# V2-2layer.net
KiCad netlist of a schematic drawn in EAGLE
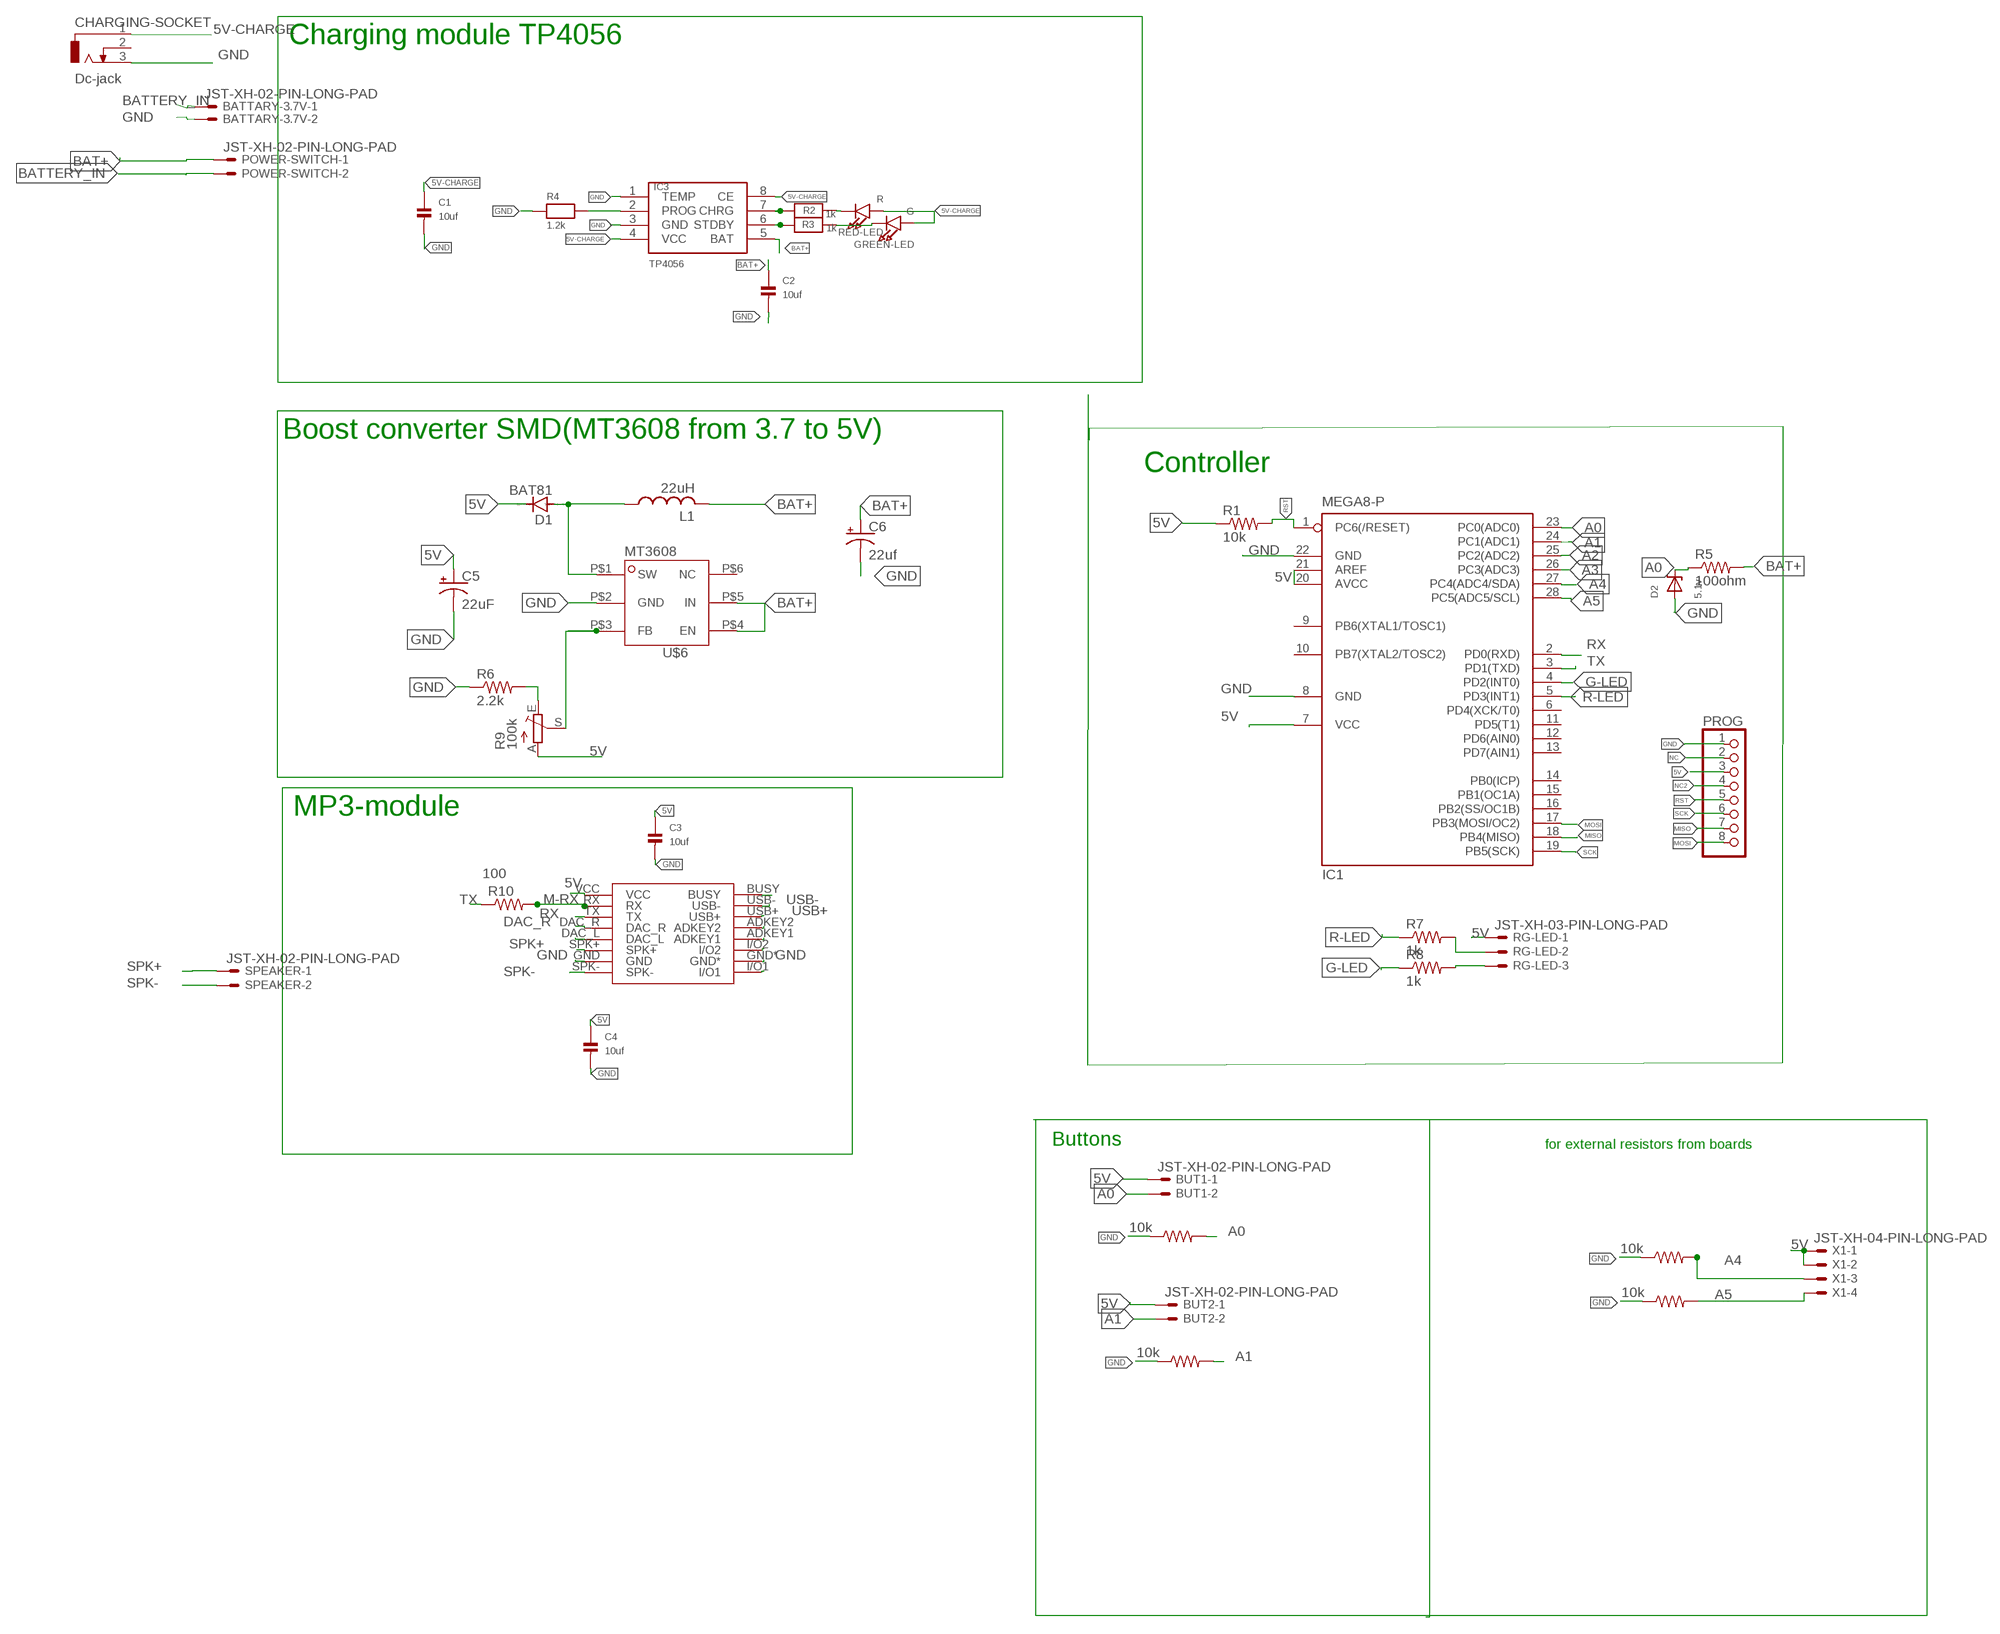
[diagram p0: schematic, sheet 1]

(export (version "E")
  (design (tool "Eeschema 10.0.6"))
  (components
    (comp (ref "BATTARY-3.7V")
      (value "JST-XH-02-PIN-LONG-PAD")
      (footprint "eagle-import:JST-XH-02-PACKAGE-LONG-PAD")
      (libsource (lib "eagle-import") (part "JST-XH-02-PIN-LONG-PAD"))
    )
    (comp (ref "BUT1")
      (value "JST-XH-02-PIN-LONG-PAD")
      (footprint "eagle-import:JST-XH-02-PACKAGE-LONG-PAD")
      (libsource (lib "eagle-import") (part "JST-XH-02-PIN-LONG-PAD"))
    )
    (comp (ref "BUT2")
      (value "JST-XH-02-PIN-LONG-PAD")
      (footprint "eagle-import:JST-XH-02-PACKAGE-LONG-PAD")
      (libsource (lib "eagle-import") (part "JST-XH-02-PIN-LONG-PAD"))
    )
    (comp (ref "C1")
      (value "10uf")
      (footprint "eagle-import:0805")
      (libsource (lib "eagle-import") (part "CAP_CERAMIC0805"))
    )
    (comp (ref "C2")
      (value "10uf")
      (footprint "eagle-import:0805")
      (libsource (lib "eagle-import") (part "CAP_CERAMIC0805"))
    )
    (comp (ref "C3")
      (value "10uf")
      (footprint "eagle-import:0805")
      (libsource (lib "eagle-import") (part "CAP_CERAMIC0805"))
    )
    (comp (ref "C4")
      (value "10uf")
      (footprint "eagle-import:0805")
      (libsource (lib "eagle-import") (part "CAP_CERAMIC0805"))
    )
    (comp (ref "C5")
      (value "22uF")
      (footprint "eagle-import:E2,5-6E")
      (libsource (lib "eagle-import") (part "CPOL-USE2,5-6E"))
    )
    (comp (ref "C6")
      (value "22uf")
      (footprint "eagle-import:E2,5-6E")
      (libsource (lib "eagle-import") (part "CPOL-USE2,5-6E"))
    )
    (comp (ref "CHARGING-SOCKET")
      (value "Dc-jack")
      (footprint "eagle-import:DCJ0303")
      (libsource (lib "eagle-import") (part "CON_JACK"))
    )
    (comp (ref "D1")
      (value "BAT81")
      (footprint "eagle-import:DO34-7")
      (libsource (lib "eagle-import") (part "BAT81"))
    )
    (comp (ref "D2")
      (value "5.1v")
      (footprint "eagle-import:SMADIODE")
      (libsource (lib "eagle-import") (part "DIODE-ZENER"))
    )
    (comp (ref "GREEN-LED")
      (value "G")
      (footprint "eagle-import:CHIPLED_0805")
      (libsource (lib "eagle-import") (part "LED0805"))
    )
    (comp (ref "IC1")
      (value "MEGA8-P")
      (footprint "eagle-import:DIL28-3")
      (libsource (lib "eagle-import") (part "MEGA8-P"))
    )
    (comp (ref "IC3")
      (value "TP4056")
      (footprint "eagle-import:SOP-8")
      (libsource (lib "eagle-import") (part "TP4056"))
    )
    (comp (ref "KEYPADS")
      (value "10k")
      (footprint "eagle-import:0204_7")
      (libsource (lib "eagle-import") (part "RES-7"))
    )
    (comp (ref "KEYPADS1")
      (value "10k")
      (footprint "eagle-import:0204_7")
      (libsource (lib "eagle-import") (part "RES-7"))
    )
    (comp (ref "KEYPADS2")
      (value "10k")
      (footprint "eagle-import:0204_7")
      (libsource (lib "eagle-import") (part "RES-7"))
    )
    (comp (ref "KEYPADS3")
      (value "10k")
      (footprint "eagle-import:0204_7")
      (libsource (lib "eagle-import") (part "RES-7"))
    )
    (comp (ref "L1")
      (value "22uH")
      (footprint "eagle-import:L1812")
      (libsource (lib "eagle-import") (part "L-USL1812"))
    )
    (comp (ref "POWER-SWITCH")
      (value "JST-XH-02-PIN-LONG-PAD")
      (footprint "eagle-import:JST-XH-02-PACKAGE-LONG-PAD")
      (libsource (lib "eagle-import") (part "JST-XH-02-PIN-LONG-PAD"))
    )
    (comp (ref "PROG")
      (value "PINHD-1X8")
      (footprint "eagle-import:1X08")
      (libsource (lib "eagle-import") (part "PINHD-1X8"))
    )
    (comp (ref "R1")
      (value "10k")
      (footprint "eagle-import:0204_7")
      (libsource (lib "eagle-import") (part "R-US_0204/7"))
    )
    (comp (ref "R2")
      (value "1k")
      (footprint "eagle-import:_0805")
      (libsource (lib "eagle-import") (part "RESISTOR_0805"))
    )
    (comp (ref "R3")
      (value "1k")
      (footprint "eagle-import:_0805")
      (libsource (lib "eagle-import") (part "RESISTOR_0805"))
    )
    (comp (ref "R4")
      (value "1.2k")
      (footprint "eagle-import:_0805")
      (libsource (lib "eagle-import") (part "RESISTOR_0805"))
    )
    (comp (ref "R5")
      (value "100ohm")
      (footprint "eagle-import:0204_7")
      (libsource (lib "eagle-import") (part "R-US_0204/7"))
    )
    (comp (ref "R6")
      (value "2.2k")
      (footprint "eagle-import:M0805")
      (libsource (lib "eagle-import") (part "R-US_M0805"))
    )
    (comp (ref "R7")
      (value "1k")
      (footprint "eagle-import:0204_7")
      (libsource (lib "eagle-import") (part "R-US_0204/7"))
    )
    (comp (ref "R8")
      (value "1k")
      (footprint "eagle-import:0204_7")
      (libsource (lib "eagle-import") (part "R-US_0204/7"))
    )
    (comp (ref "R9")
      (value "100k")
      (footprint "eagle-import:B25U")
      (libsource (lib "eagle-import") (part "TRIM_EU-B25U"))
    )
    (comp (ref "R10")
      (value "100")
      (footprint "eagle-import:0204_7")
      (libsource (lib "eagle-import") (part "RES-7"))
    )
    (comp (ref "RED-LED")
      (value "R")
      (footprint "eagle-import:CHIPLED_0805")
      (libsource (lib "eagle-import") (part "LED0805"))
    )
    (comp (ref "RG-LED")
      (value "JST-XH-03-PIN-LONG-PAD")
      (footprint "eagle-import:JST-XH-03-PACKAGE-LONG-PAD")
      (libsource (lib "eagle-import") (part "JST-XH-03-PIN-LONG-PAD"))
    )
    (comp (ref "SPEAKER")
      (value "JST-XH-02-PIN-LONG-PAD")
      (footprint "eagle-import:JST-XH-02-PACKAGE-LONG-PAD")
      (libsource (lib "eagle-import") (part "JST-XH-02-PIN-LONG-PAD"))
    )
    (comp (ref "U$2")
      (value "MP3_MODULE")
      (footprint "eagle-import:MP3_MODULE")
      (libsource (lib "eagle-import") (part "MP3_MODULE"))
    )
    (comp (ref "U$6")
      (value "MT3608SOT23-6")
      (footprint "eagle-import:SOT23-6")
      (libsource (lib "eagle-import") (part "MT3608SOT23-6"))
    )
    (comp (ref "X1")
      (value "JST-XH-04-PIN-LONG-PAD")
      (footprint "eagle-import:JST-XH-04-PACKAGE-LONG-PAD")
      (libsource (lib "eagle-import") (part "JST-XH-04-PIN-LONG-PAD"))
    )
  )
  (nets
    (net (code "1") (name "/DAC_R") (class "Default")
      (node (ref "U$2") (pin "DAC_R") (pinfunction "DAC_R_DAC_R") (pintype "bidirectional"))
    )
    (net (code "2") (name "/M-RX") (class "Default")
      (node (ref "R10") (pin "2") (pinfunction "2_2") (pintype "passive"))
      (node (ref "U$2") (pin "RX") (pinfunction "RX_RX") (pintype "bidirectional"))
    )
    (net (code "3") (name "/RX") (class "Default")
      (node (ref "IC1") (pin "2") (pinfunction "PD0(RXD)_2") (pintype "bidirectional"))
      (node (ref "U$2") (pin "TX") (pinfunction "TX_TX") (pintype "bidirectional"))
    )
    (net (code "4") (name "/SPK+") (class "Default")
      (node (ref "SPEAKER") (pin "1") (pinfunction "S_1") (pintype "passive"))
      (node (ref "U$2") (pin "SPK+") (pinfunction "SPK+_SPK+") (pintype "bidirectional"))
    )
    (net (code "5") (name "/SPK-") (class "Default")
      (node (ref "SPEAKER") (pin "2") (pinfunction "S_2") (pintype "passive"))
      (node (ref "U$2") (pin "SPK-") (pinfunction "SPK-_SPK-") (pintype "bidirectional"))
    )
    (net (code "6") (name "/TX") (class "Default")
      (node (ref "IC1") (pin "3") (pinfunction "PD1(TXD)_3") (pintype "bidirectional"))
      (node (ref "R10") (pin "1") (pinfunction "1_1") (pintype "passive"))
    )
    (net (code "7") (name "/USB+") (class "Default")
      (node (ref "U$2") (pin "USB+") (pinfunction "USB+_USB+") (pintype "bidirectional"))
    )
    (net (code "8") (name "/USB-") (class "Default")
      (node (ref "U$2") (pin "USB-") (pinfunction "USB-_USB-") (pintype "bidirectional"))
    )
    (net (code "9") (name "5V") (class "Default")
      (node (ref "BUT1") (pin "1") (pinfunction "S_1") (pintype "passive"))
      (node (ref "BUT2") (pin "1") (pinfunction "S_1") (pintype "passive"))
      (node (ref "C3") (pin "1") (pinfunction "P$1_1") (pintype "passive"))
      (node (ref "C4") (pin "1") (pinfunction "P$1_1") (pintype "passive"))
      (node (ref "C5") (pin "+") (pinfunction "+_+") (pintype "passive"))
      (node (ref "D1") (pin "C") (pinfunction "C_C") (pintype "passive"))
      (node (ref "IC1") (pin "20") (pinfunction "AVCC_20") (pintype "power_in"))
      (node (ref "IC1") (pin "21") (pinfunction "AREF_21") (pintype "passive"))
      (node (ref "IC1") (pin "7") (pinfunction "VCC_7") (pintype "power_in"))
      (node (ref "PROG") (pin "3") (pinfunction "3_3") (pintype "passive"))
      (node (ref "R1") (pin "1") (pinfunction "1_1") (pintype "passive"))
      (node (ref "R9") (pin "A") (pinfunction "A_A") (pintype "passive"))
      (node (ref "RG-LED") (pin "1") (pinfunction "S_1") (pintype "passive"))
      (node (ref "U$2") (pin "VCC") (pinfunction "VCC_VCC") (pintype "bidirectional"))
      (node (ref "X1") (pin "1") (pinfunction "S_1") (pintype "passive"))
      (node (ref "X1") (pin "2") (pinfunction "S_2") (pintype "passive"))
    )
    (net (code "10") (name "5V-CHARGE") (class "Default")
      (node (ref "C1") (pin "1") (pinfunction "P$1_1") (pintype "passive"))
      (node (ref "CHARGING-SOCKET") (pin "1") (pinfunction "1_1") (pintype "passive"))
      (node (ref "GREEN-LED") (pin "A") (pinfunction "A_A") (pintype "passive"))
      (node (ref "IC3") (pin "4") (pinfunction "VCC_4") (pintype "bidirectional"))
      (node (ref "IC3") (pin "8") (pinfunction "CE_8") (pintype "bidirectional"))
      (node (ref "RED-LED") (pin "A") (pinfunction "A_A") (pintype "passive"))
    )
    (net (code "11") (name "A0") (class "Default")
      (node (ref "BUT1") (pin "2") (pinfunction "S_2") (pintype "passive"))
      (node (ref "D2") (pin "C") (pinfunction "C_C") (pintype "passive"))
      (node (ref "IC1") (pin "23") (pinfunction "PC0(ADC0)_23") (pintype "bidirectional"))
      (node (ref "KEYPADS") (pin "2") (pinfunction "2_2") (pintype "passive"))
      (node (ref "R5") (pin "1") (pinfunction "1_1") (pintype "passive"))
    )
    (net (code "12") (name "A1") (class "Default")
      (node (ref "BUT2") (pin "2") (pinfunction "S_2") (pintype "passive"))
      (node (ref "IC1") (pin "24") (pinfunction "PC1(ADC1)_24") (pintype "bidirectional"))
      (node (ref "KEYPADS3") (pin "2") (pinfunction "2_2") (pintype "passive"))
    )
    (net (code "13") (name "A2") (class "Default")
      (node (ref "IC1") (pin "25") (pinfunction "PC2(ADC2)_25") (pintype "bidirectional"))
    )
    (net (code "14") (name "A3") (class "Default")
      (node (ref "IC1") (pin "26") (pinfunction "PC3(ADC3)_26") (pintype "bidirectional"))
    )
    (net (code "15") (name "A4") (class "Default")
      (node (ref "IC1") (pin "27") (pinfunction "PC4(ADC4/SDA)_27") (pintype "bidirectional"))
      (node (ref "KEYPADS1") (pin "2") (pinfunction "2_2") (pintype "passive"))
      (node (ref "X1") (pin "3") (pinfunction "S_3") (pintype "passive"))
    )
    (net (code "16") (name "A5") (class "Default")
      (node (ref "IC1") (pin "28") (pinfunction "PC5(ADC5/SCL)_28") (pintype "bidirectional"))
      (node (ref "KEYPADS2") (pin "2") (pinfunction "2_2") (pintype "passive"))
      (node (ref "X1") (pin "4") (pinfunction "S_4") (pintype "passive"))
    )
    (net (code "17") (name "BAT+") (class "Default")
      (node (ref "C2") (pin "1") (pinfunction "P$1_1") (pintype "passive"))
      (node (ref "C6") (pin "+") (pinfunction "+_+") (pintype "passive"))
      (node (ref "IC3") (pin "5") (pinfunction "BAT_5") (pintype "bidirectional"))
      (node (ref "L1") (pin "2") (pinfunction "2_2") (pintype "passive"))
      (node (ref "POWER-SWITCH") (pin "1") (pinfunction "S_1") (pintype "passive"))
      (node (ref "R5") (pin "2") (pinfunction "2_2") (pintype "passive"))
      (node (ref "U$6") (pin "P$4") (pinfunction "EN_P$4") (pintype "bidirectional"))
      (node (ref "U$6") (pin "P$5") (pinfunction "IN_P$5") (pintype "bidirectional"))
    )
    (net (code "18") (name "BATTERY_IN") (class "Default")
      (node (ref "BATTARY-3.7V") (pin "1") (pinfunction "S_1") (pintype "passive"))
      (node (ref "POWER-SWITCH") (pin "2") (pinfunction "S_2") (pintype "passive"))
    )
    (net (code "19") (name "G-LED") (class "Default")
      (node (ref "IC1") (pin "4") (pinfunction "PD2(INT0)_4") (pintype "bidirectional"))
      (node (ref "R8") (pin "1") (pinfunction "1_1") (pintype "passive"))
    )
    (net (code "20") (name "GND") (class "Default")
      (node (ref "BATTARY-3.7V") (pin "2") (pinfunction "S_2") (pintype "passive"))
      (node (ref "C1") (pin "2") (pinfunction "P$2_2") (pintype "passive"))
      (node (ref "C2") (pin "2") (pinfunction "P$2_2") (pintype "passive"))
      (node (ref "C3") (pin "2") (pinfunction "P$2_2") (pintype "passive"))
      (node (ref "C4") (pin "2") (pinfunction "P$2_2") (pintype "passive"))
      (node (ref "C5") (pin "-") (pinfunction "-_-") (pintype "passive"))
      (node (ref "C6") (pin "-") (pinfunction "-_-") (pintype "passive"))
      (node (ref "CHARGING-SOCKET") (pin "3") (pinfunction "3_3") (pintype "passive"))
      (node (ref "D2") (pin "A") (pinfunction "A_A") (pintype "passive"))
      (node (ref "IC1") (pin "22") (pinfunction "GND_22") (pintype "power_in"))
      (node (ref "IC1") (pin "8") (pinfunction "GND_8") (pintype "power_in"))
      (node (ref "IC3") (pin "1") (pinfunction "TEMP_1") (pintype "bidirectional"))
      (node (ref "IC3") (pin "3") (pinfunction "GND_3") (pintype "bidirectional"))
      (node (ref "KEYPADS") (pin "1") (pinfunction "1_1") (pintype "passive"))
      (node (ref "KEYPADS1") (pin "1") (pinfunction "1_1") (pintype "passive"))
      (node (ref "KEYPADS2") (pin "1") (pinfunction "1_1") (pintype "passive"))
      (node (ref "KEYPADS3") (pin "1") (pinfunction "1_1") (pintype "passive"))
      (node (ref "PROG") (pin "1") (pinfunction "1_1") (pintype "passive"))
      (node (ref "R4") (pin "1") (pinfunction "1_1") (pintype "passive"))
      (node (ref "R6") (pin "1") (pinfunction "1_1") (pintype "passive"))
      (node (ref "U$2") (pin "GND") (pinfunction "GND_GND") (pintype "bidirectional"))
      (node (ref "U$2") (pin "GND*") (pinfunction "GND*_GND*") (pintype "bidirectional"))
      (node (ref "U$6") (pin "P$2") (pinfunction "GND_P$2") (pintype "bidirectional"))
    )
    (net (code "21") (name "MISO") (class "Default")
      (node (ref "IC1") (pin "18") (pinfunction "PB4(MISO)_18") (pintype "bidirectional"))
      (node (ref "PROG") (pin "7") (pinfunction "7_7") (pintype "passive"))
    )
    (net (code "22") (name "MOSI") (class "Default")
      (node (ref "IC1") (pin "17") (pinfunction "PB3(MOSI/OC2)_17") (pintype "bidirectional"))
      (node (ref "PROG") (pin "8") (pinfunction "8_8") (pintype "passive"))
    )
    (net (code "23") (name "NC") (class "Default")
      (node (ref "PROG") (pin "2") (pinfunction "2_2") (pintype "passive"))
    )
    (net (code "24") (name "NC2") (class "Default")
      (node (ref "PROG") (pin "4") (pinfunction "4_4") (pintype "passive"))
    )
    (net (code "25") (name "Net-(GREEN-LED-PadC)") (class "Default")
      (node (ref "GREEN-LED") (pin "C") (pinfunction "C_C") (pintype "passive"))
      (node (ref "R3") (pin "2") (pinfunction "2_2") (pintype "passive"))
    )
    (net (code "26") (name "Net-(IC3-CHRG)") (class "Default")
      (node (ref "IC3") (pin "7") (pinfunction "CHRG_7") (pintype "bidirectional"))
      (node (ref "R2") (pin "1") (pinfunction "1_1") (pintype "passive"))
    )
    (net (code "27") (name "Net-(IC3-PROG)") (class "Default")
      (node (ref "IC3") (pin "2") (pinfunction "PROG_2") (pintype "bidirectional"))
      (node (ref "R4") (pin "2") (pinfunction "2_2") (pintype "passive"))
    )
    (net (code "28") (name "Net-(IC3-STDBY)") (class "Default")
      (node (ref "IC3") (pin "6") (pinfunction "STDBY_6") (pintype "bidirectional"))
      (node (ref "R3") (pin "1") (pinfunction "1_1") (pintype "passive"))
    )
    (net (code "29") (name "Net-(R2-Pad2)") (class "Default")
      (node (ref "R2") (pin "2") (pinfunction "2_2") (pintype "passive"))
      (node (ref "RED-LED") (pin "C") (pinfunction "C_C") (pintype "passive"))
    )
    (net (code "30") (name "Net-(R6-Pad2)") (class "Default")
      (node (ref "R6") (pin "2") (pinfunction "2_2") (pintype "passive"))
      (node (ref "R9") (pin "E") (pinfunction "E_E") (pintype "passive"))
    )
    (net (code "31") (name "Net-(RG-LEDB-S)") (class "Default")
      (node (ref "R7") (pin "2") (pinfunction "2_2") (pintype "passive"))
      (node (ref "RG-LED") (pin "2") (pinfunction "S_2") (pintype "passive"))
    )
    (net (code "32") (name "Net-(RG-LEDC-S)") (class "Default")
      (node (ref "R8") (pin "2") (pinfunction "2_2") (pintype "passive"))
      (node (ref "RG-LED") (pin "3") (pinfunction "S_3") (pintype "passive"))
    )
    (net (code "33") (name "Net-(U$6-FB)") (class "Default")
      (node (ref "R9") (pin "S") (pinfunction "S_S") (pintype "passive"))
      (node (ref "U$6") (pin "P$3") (pinfunction "FB_P$3") (pintype "bidirectional"))
    )
    (net (code "34") (name "Net-(U$6-SW)") (class "Default")
      (node (ref "D1") (pin "A") (pinfunction "A_A") (pintype "passive"))
      (node (ref "L1") (pin "1") (pinfunction "1_1") (pintype "passive"))
      (node (ref "U$6") (pin "P$1") (pinfunction "SW_P$1") (pintype "bidirectional"))
    )
    (net (code "35") (name "R-LED") (class "Default")
      (node (ref "IC1") (pin "5") (pinfunction "PD3(INT1)_5") (pintype "bidirectional"))
      (node (ref "R7") (pin "1") (pinfunction "1_1") (pintype "passive"))
    )
    (net (code "36") (name "RST") (class "Default")
      (node (ref "IC1") (pin "1") (pinfunction "PC6(/RESET)_1") (pintype "bidirectional"))
      (node (ref "PROG") (pin "5") (pinfunction "5_5") (pintype "passive"))
      (node (ref "R1") (pin "2") (pinfunction "2_2") (pintype "passive"))
    )
    (net (code "37") (name "SCK") (class "Default")
      (node (ref "IC1") (pin "19") (pinfunction "PB5(SCK)_19") (pintype "bidirectional"))
      (node (ref "PROG") (pin "6") (pinfunction "6_6") (pintype "passive"))
    )
    (net (code "38") (name "unconnected-(CHARGING-SOCKET-Pad2)") (class "Default")
      (node (ref "CHARGING-SOCKET") (pin "2") (pinfunction "2_2") (pintype "passive"))
    )
    (net (code "39") (name "unconnected-(IC1-PB0(ICP)-Pad14)") (class "Default")
      (node (ref "IC1") (pin "14") (pinfunction "PB0(ICP)_14") (pintype "bidirectional"))
    )
    (net (code "40") (name "unconnected-(IC1-PB1(OC1A)-Pad15)") (class "Default")
      (node (ref "IC1") (pin "15") (pinfunction "PB1(OC1A)_15") (pintype "bidirectional"))
    )
    (net (code "41") (name "unconnected-(IC1-PB2(SS{slash}OC1B)-Pad16)") (class "Default")
      (node (ref "IC1") (pin "16") (pinfunction "PB2(SS/OC1B)_16") (pintype "bidirectional"))
    )
    (net (code "42") (name "unconnected-(IC1-PB6(XTAL1{slash}TOSC1)-Pad9)") (class "Default")
      (node (ref "IC1") (pin "9") (pinfunction "PB6(XTAL1/TOSC1)_9") (pintype "bidirectional"))
    )
    (net (code "43") (name "unconnected-(IC1-PB7(XTAL2{slash}TOSC2)-Pad10)") (class "Default")
      (node (ref "IC1") (pin "10") (pinfunction "PB7(XTAL2/TOSC2)_10") (pintype "bidirectional"))
    )
    (net (code "44") (name "unconnected-(IC1-PD4(XCK{slash}T0)-Pad6)") (class "Default")
      (node (ref "IC1") (pin "6") (pinfunction "PD4(XCK/T0)_6") (pintype "bidirectional"))
    )
    (net (code "45") (name "unconnected-(IC1-PD5(T1)-Pad11)") (class "Default")
      (node (ref "IC1") (pin "11") (pinfunction "PD5(T1)_11") (pintype "bidirectional"))
    )
    (net (code "46") (name "unconnected-(IC1-PD6(AIN0)-Pad12)") (class "Default")
      (node (ref "IC1") (pin "12") (pinfunction "PD6(AIN0)_12") (pintype "bidirectional"))
    )
    (net (code "47") (name "unconnected-(IC1-PD7(AIN1)-Pad13)") (class "Default")
      (node (ref "IC1") (pin "13") (pinfunction "PD7(AIN1)_13") (pintype "bidirectional"))
    )
    (net (code "48") (name "unconnected-(U$2-PadADKEY1)") (class "Default")
      (node (ref "U$2") (pin "ADKEY1") (pinfunction "ADKEY1_ADKEY1") (pintype "bidirectional"))
    )
    (net (code "49") (name "unconnected-(U$2-PadADKEY2)") (class "Default")
      (node (ref "U$2") (pin "ADKEY2") (pinfunction "ADKEY2_ADKEY2") (pintype "bidirectional"))
    )
    (net (code "50") (name "unconnected-(U$2-PadBUSY)") (class "Default")
      (node (ref "U$2") (pin "BUSY") (pinfunction "BUSY_BUSY") (pintype "bidirectional"))
    )
    (net (code "51") (name "unconnected-(U$2-PadDAC_L)") (class "Default")
      (node (ref "U$2") (pin "DAC_L") (pinfunction "DAC_L_DAC_L") (pintype "bidirectional"))
    )
    (net (code "52") (name "unconnected-(U$2-PadI{slash}O1)") (class "Default")
      (node (ref "U$2") (pin "I/O1") (pinfunction "I/O1_I/O1") (pintype "bidirectional"))
    )
    (net (code "53") (name "unconnected-(U$2-PadI{slash}O2)") (class "Default")
      (node (ref "U$2") (pin "I/O2") (pinfunction "I/O2_I/O2") (pintype "bidirectional"))
    )
    (net (code "54") (name "unconnected-(U$6-NC-PadP$6)") (class "Default")
      (node (ref "U$6") (pin "P$6") (pinfunction "NC_P$6") (pintype "bidirectional"))
    )
  )
)
